# 03_POWER.net
KiCad netlist of a schematic drawn in Altium Designer
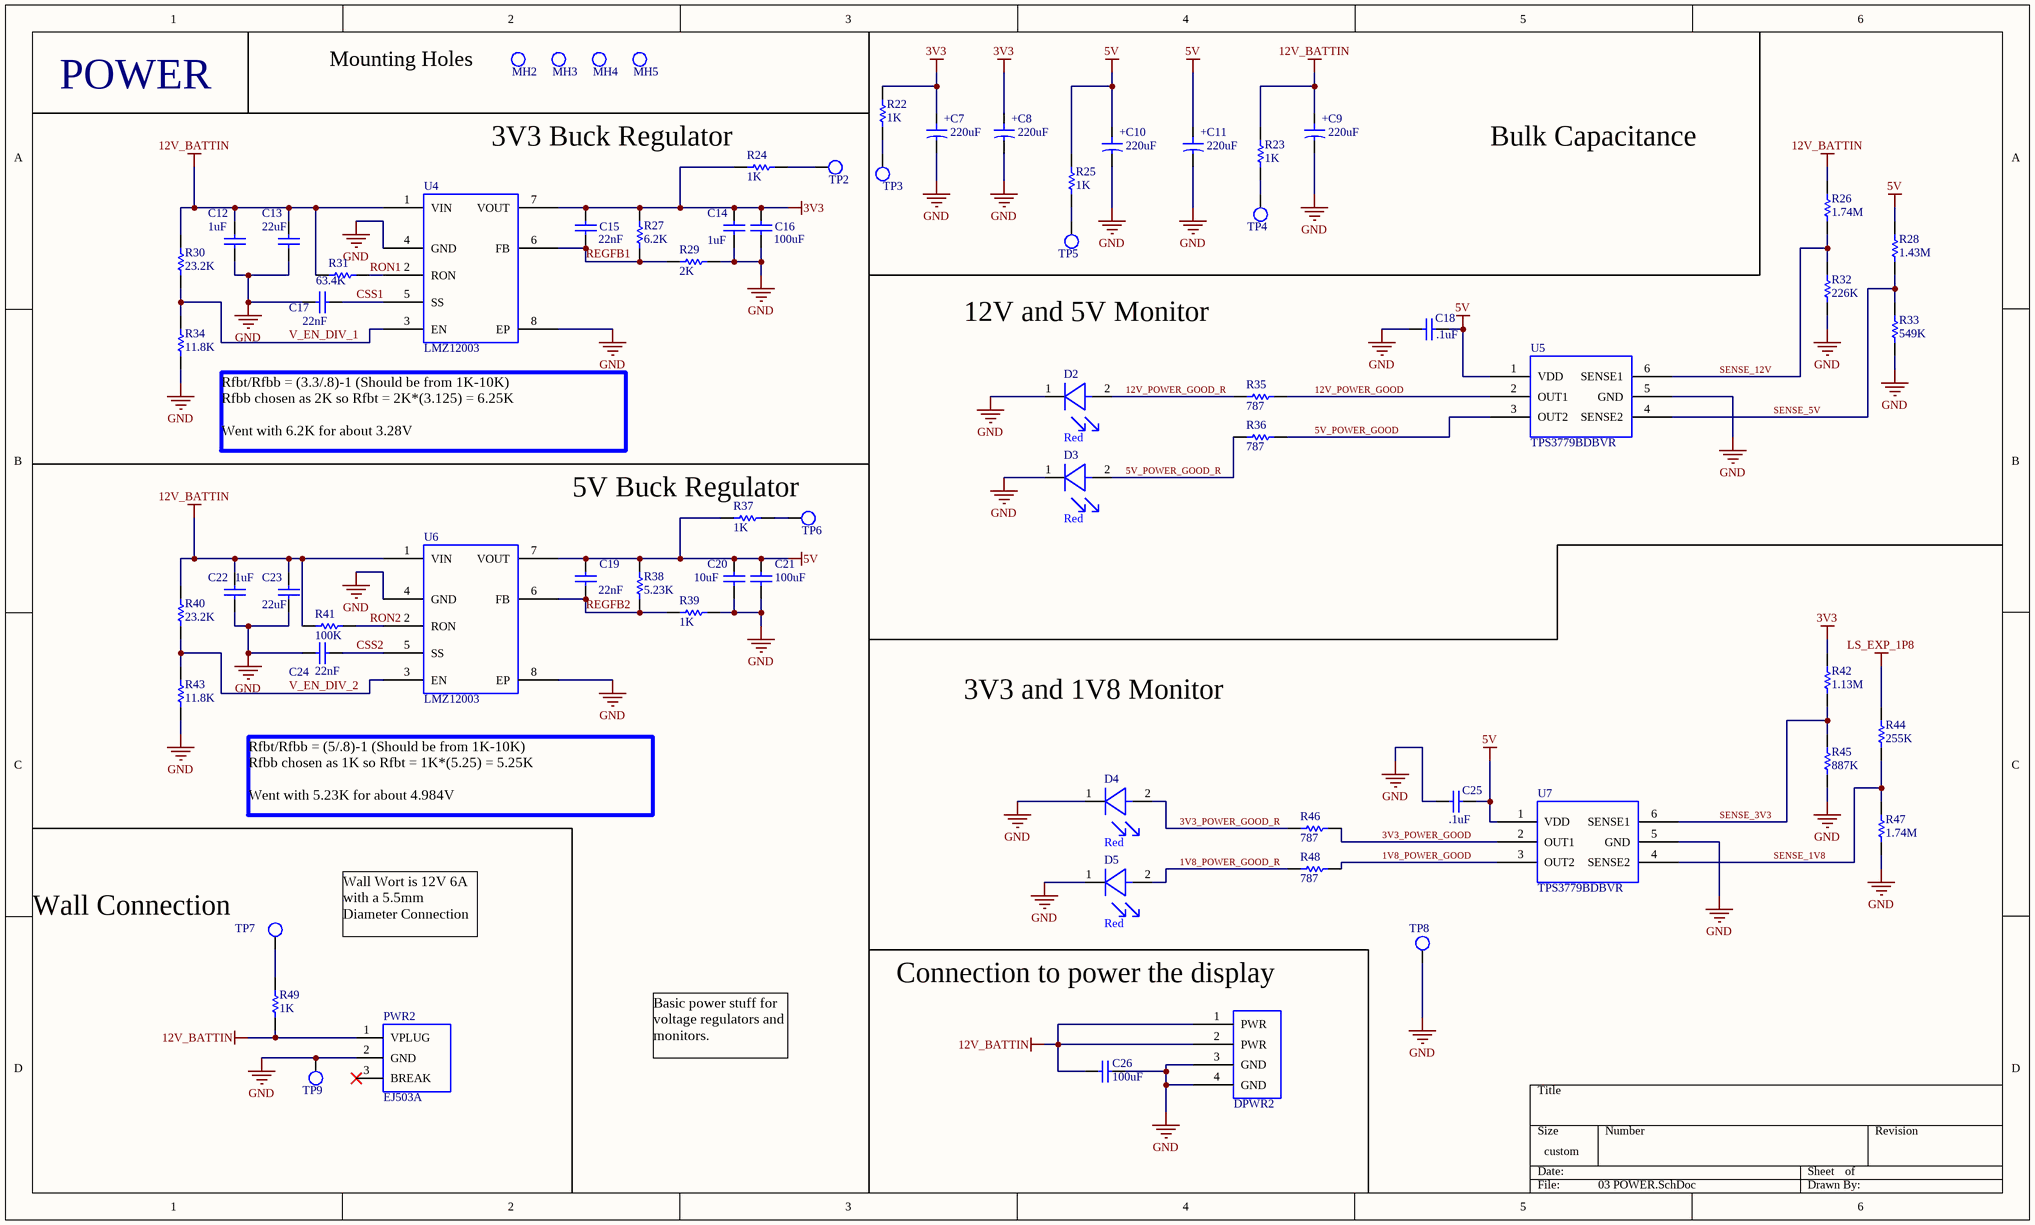
[diagram p0: 03 POWER.SchDoc]

(export (version "E")
  (design (tool "Eeschema 10.0.6"))
  (components
    (comp (ref "C7")
      (value "CAP ALUM 220UF 20% 25V SMD")
      (footprint "CAP_RADIAL")
      (fields
        (field (name "MANUFACTURER") "Nichicon")
        (field (name "MANUFACTURER PART NUMBER") "UWT1E221MNL1GS")
        (field (name "TOLERANCE") "20%")
        (field (name "CAPACITANCE") "220uF")
      )
      (libsource (lib "schlib_truman") (part "CAP_RAD_220u_25V"))
    )
    (comp (ref "C8")
      (value "CAP ALUM 220UF 20% 25V SMD")
      (footprint "CAP_RADIAL")
      (fields
        (field (name "MANUFACTURER") "Nichicon")
        (field (name "MANUFACTURER PART NUMBER") "UWT1E221MNL1GS")
        (field (name "TOLERANCE") "20%")
        (field (name "CAPACITANCE") "220uF")
      )
      (libsource (lib "schlib_truman") (part "CAP_RAD_220u_25V"))
    )
    (comp (ref "C9")
      (value "CAP ALUM 220UF 20% 25V SMD")
      (footprint "CAP_RADIAL")
      (fields
        (field (name "MANUFACTURER") "Nichicon")
        (field (name "MANUFACTURER PART NUMBER") "UWT1E221MNL1GS")
        (field (name "TOLERANCE") "20%")
        (field (name "CAPACITANCE") "220uF")
      )
      (libsource (lib "schlib_truman") (part "CAP_RAD_220u_25V"))
    )
    (comp (ref "C10")
      (value "CAP ALUM 220UF 20% 25V SMD")
      (footprint "CAP_RADIAL")
      (fields
        (field (name "MANUFACTURER") "Nichicon")
        (field (name "MANUFACTURER PART NUMBER") "UWT1E221MNL1GS")
        (field (name "TOLERANCE") "20%")
        (field (name "CAPACITANCE") "220uF")
      )
      (libsource (lib "schlib_truman") (part "CAP_RAD_220u_25V"))
    )
    (comp (ref "C11")
      (value "CAP ALUM 220UF 20% 25V SMD")
      (footprint "CAP_RADIAL")
      (fields
        (field (name "MANUFACTURER") "Nichicon")
        (field (name "MANUFACTURER PART NUMBER") "UWT1E221MNL1GS")
        (field (name "TOLERANCE") "20%")
        (field (name "CAPACITANCE") "220uF")
      )
      (libsource (lib "schlib_truman") (part "CAP_RAD_220u_25V"))
    )
    (comp (ref "C12")
      (value "1uF")
      (footprint "CAPC2012X135N")
      (description "CAP CER 1UF 100V X7S 0805")
      (fields
        (field (name "MANUFACTURER") "TDK")
        (field (name "MANUFACTURER PART NUMBER") "C2012X7S2A105K125AE")
      )
      (libsource (lib "schlib_truman") (part "CAP_0805_1u_100V"))
    )
    (comp (ref "C13")
      (value "22uF")
      (footprint "CAPC2012X135N")
      (fields
        (field (name "MANUFACTURER") "Samsung")
        (field (name "MANUFACTURER PART NUMBER") "CL21A226MAQNNNE")
        (field (name "TOLERANCE") "20%")
      )
      (libsource (lib "schlib_truman") (part "CAP_0805_22u_25V"))
    )
    (comp (ref "C14")
      (value "1uF")
      (footprint "CAPC2012X135N")
      (description "CAP CER 1UF 100V X7S 0805")
      (fields
        (field (name "MANUFACTURER") "TDK")
        (field (name "MANUFACTURER PART NUMBER") "C2012X7S2A105K125AE")
      )
      (libsource (lib "schlib_truman") (part "CAP_0805_1u_100V"))
    )
    (comp (ref "C15")
      (value "22nF")
      (footprint "CAPC2012X135N")
      (description "CAP CER 0.022UF 100V X7R 0805")
      (fields
        (field (name "MANUFACTURER") "TDK")
        (field (name "MANUFACTURER PART NUMBER") "CGJ4J2X7R2A223K125AA")
      )
      (libsource (lib "schlib_truman") (part "CAP_0805_22n_100V"))
    )
    (comp (ref "C16")
      (value "100uF")
      (footprint "FP_1210")
      (description "Cap Ceramic 100uF 10V X5R 20% SMD 1210 85C Embossed T/R")
      (fields
        (field (name "MANUFACTURER") "Murata")
        (field (name "MANUFACTURER PART NUMBER") "GRM32ER61A107ME20L")
      )
      (libsource (lib "schlib_truman") (part "CAP_1210_100u_10V"))
    )
    (comp (ref "C17")
      (value "22nF")
      (footprint "CAPC2012X135N")
      (description "CAP CER 0.022UF 100V X7R 0805")
      (fields
        (field (name "MANUFACTURER") "TDK")
        (field (name "MANUFACTURER PART NUMBER") "CGJ4J2X7R2A223K125AA")
      )
      (libsource (lib "schlib_truman") (part "CAP_0805_22n_100V"))
    )
    (comp (ref "C18")
      (value ".1uF")
      (footprint "CAPC2012X135N")
      (description "Cap Ceramic 0.1uF 250V X7T 10% SMD 0805 125C Plastic T/R")
      (fields
        (field (name "MANUFACTURER") "TDK")
        (field (name "MANUFACTURER PART NUMBER") "C2012X7T2E104K125AE")
      )
      (libsource (lib "schlib_truman") (part "CAP_0805_.1u_250V"))
    )
    (comp (ref "C19")
      (value "22nF")
      (footprint "CAPC2012X135N")
      (description "CAP CER 0.022UF 100V X7R 0805")
      (fields
        (field (name "MANUFACTURER") "TDK")
        (field (name "MANUFACTURER PART NUMBER") "CGJ4J2X7R2A223K125AA")
      )
      (libsource (lib "schlib_truman") (part "CAP_0805_22n_100V"))
    )
    (comp (ref "C20")
      (value "10uF")
      (footprint "CAPC2012X135N")
      (description "Cap Ceramic 10uF 16V X5R 10% SMD 0805 85C T/R")
      (fields
        (field (name "MANUFACTURER") "Johanson Dielectrics")
        (field (name "MANUFACTURER PART NUMBER") "160R15X106KV4E")
      )
      (libsource (lib "schlib_truman") (part "CAP_0805_10u_16V"))
    )
    (comp (ref "C21")
      (value "100uF")
      (footprint "FP_1210")
      (description "Cap Ceramic 100uF 10V X5R 20% SMD 1210 85C Embossed T/R")
      (fields
        (field (name "MANUFACTURER") "Murata")
        (field (name "MANUFACTURER PART NUMBER") "GRM32ER61A107ME20L")
      )
      (libsource (lib "schlib_truman") (part "CAP_1210_100u_10V"))
    )
    (comp (ref "C22")
      (value "1uF")
      (footprint "CAPC2012X135N")
      (description "CAP CER 1UF 100V X7S 0805")
      (fields
        (field (name "MANUFACTURER") "TDK")
        (field (name "MANUFACTURER PART NUMBER") "C2012X7S2A105K125AE")
      )
      (libsource (lib "schlib_truman") (part "CAP_0805_1u_100V"))
    )
    (comp (ref "C23")
      (value "22uF")
      (footprint "CAPC2012X135N")
      (fields
        (field (name "MANUFACTURER") "Samsung")
        (field (name "MANUFACTURER PART NUMBER") "CL21A226MAQNNNE")
        (field (name "TOLERANCE") "20%")
      )
      (libsource (lib "schlib_truman") (part "CAP_0805_22u_25V"))
    )
    (comp (ref "C24")
      (value "22nF")
      (footprint "CAPC2012X135N")
      (description "CAP CER 0.022UF 100V X7R 0805")
      (fields
        (field (name "MANUFACTURER") "TDK")
        (field (name "MANUFACTURER PART NUMBER") "CGJ4J2X7R2A223K125AA")
      )
      (libsource (lib "schlib_truman") (part "CAP_0805_22n_100V"))
    )
    (comp (ref "C25")
      (value ".1uF")
      (footprint "CAPC2012X135N")
      (description "Cap Ceramic 0.1uF 250V X7T 10% SMD 0805 125C Plastic T/R")
      (fields
        (field (name "MANUFACTURER") "TDK")
        (field (name "MANUFACTURER PART NUMBER") "C2012X7T2E104K125AE")
      )
      (libsource (lib "schlib_truman") (part "CAP_0805_.1u_250V"))
    )
    (comp (ref "C26")
      (value "100uF")
      (footprint "FP_1210")
      (description "Cap Ceramic 100uF 10V X5R 20% SMD 1210 85C Embossed T/R")
      (fields
        (field (name "MANUFACTURER") "Murata")
        (field (name "MANUFACTURER PART NUMBER") "GRM32ER61A107ME20L")
      )
      (libsource (lib "schlib_truman") (part "CAP_1210_100u_10V"))
    )
    (comp (ref "D2")
      (value "LED_RED_636nm")
      (footprint "POWERLED_FP")
      (description "Standard LEDs - SMD Surface Mount LEDs")
      (fields
        (field (name "COLOR") "Red")
        (field (name "MANUFACTURER") "Lumex")
        (field (name "MANUFACTURER PART NUMBER") "SML-LXR85SIC-TR")
      )
      (libsource (lib "schlib_truman") (part "LED_RED_636nm"))
    )
    (comp (ref "D3")
      (value "LED_RED_636nm")
      (footprint "POWERLED_FP")
      (description "Standard LEDs - SMD Surface Mount LEDs")
      (fields
        (field (name "COLOR") "Red")
        (field (name "MANUFACTURER") "Lumex")
        (field (name "MANUFACTURER PART NUMBER") "SML-LXR85SIC-TR")
      )
      (libsource (lib "schlib_truman") (part "LED_RED_636nm"))
    )
    (comp (ref "D4")
      (value "LED_RED_636nm")
      (footprint "POWERLED_FP")
      (description "Standard LEDs - SMD Surface Mount LEDs")
      (fields
        (field (name "COLOR") "Red")
        (field (name "MANUFACTURER") "Lumex")
        (field (name "MANUFACTURER PART NUMBER") "SML-LXR85SIC-TR")
      )
      (libsource (lib "schlib_truman") (part "LED_RED_636nm"))
    )
    (comp (ref "D5")
      (value "LED_RED_636nm")
      (footprint "POWERLED_FP")
      (description "Standard LEDs - SMD Surface Mount LEDs")
      (fields
        (field (name "COLOR") "Red")
        (field (name "MANUFACTURER") "Lumex")
        (field (name "MANUFACTURER PART NUMBER") "SML-LXR85SIC-TR")
      )
      (libsource (lib "schlib_truman") (part "LED_RED_636nm"))
    )
    (comp (ref "DPWR2")
      (value "Display_Power")
      (footprint "PHOENIX_4POS_1935187")
      (description "4 Position Thru Hole Connection")
      (fields
        (field (name "MANUFACTURER") "Phoenix Contact")
        (field (name "MANUFACTURER PART NUMBER") "1935187")
      )
      (libsource (lib "schlib_truman") (part "Display_Power"))
    )
    (comp (ref "MH2")
      (value "MOUNTINGHOLE")
      (footprint "MOUNTINGHOLE")
      (description "Mounting Hole For Board")
      (libsource (lib "schlib_truman") (part "MOUNTINGHOLE"))
    )
    (comp (ref "MH3")
      (value "MOUNTINGHOLE")
      (footprint "MOUNTINGHOLE")
      (description "Mounting Hole For Board")
      (libsource (lib "schlib_truman") (part "MOUNTINGHOLE"))
    )
    (comp (ref "MH4")
      (value "MOUNTINGHOLE")
      (footprint "MOUNTINGHOLE")
      (description "Mounting Hole For Board")
      (libsource (lib "schlib_truman") (part "MOUNTINGHOLE"))
    )
    (comp (ref "MH5")
      (value "MOUNTINGHOLE")
      (footprint "MOUNTINGHOLE")
      (description "Mounting Hole For Board")
      (libsource (lib "schlib_truman") (part "MOUNTINGHOLE"))
    )
    (comp (ref "PWR2")
      (value "EJ503A")
      (footprint "BARRELJACK")
      (description "DC Barrel Jack 2.1mm x 5.5mm 12V 5A")
      (fields (field (name "MANUFACTURER") "Memory Protection Devices"))
      (libsource (lib "schlib_truman") (part "EJ503A"))
    )
    (comp (ref "R22")
      (value "RES_0805_1K")
      (footprint "RES0805")
      (description "RES SMD 1K OHM 1% 1/8W 0805")
      (fields
        (field (name "MANUFACTURER") "Yageo")
        (field (name "MANUFACTURER PART NUMBER") "RC0805FR-071KL")
        (field (name "ALTIUM_UNNAMED_1") "1K")
      )
      (libsource (lib "schlib_truman") (part "RES_0805_1K"))
    )
    (comp (ref "R23")
      (value "RES_0805_1K")
      (footprint "RES0805")
      (description "RES SMD 1K OHM 1% 1/8W 0805")
      (fields
        (field (name "MANUFACTURER") "Yageo")
        (field (name "MANUFACTURER PART NUMBER") "RC0805FR-071KL")
        (field (name "ALTIUM_UNNAMED_1") "1K")
      )
      (libsource (lib "schlib_truman") (part "RES_0805_1K"))
    )
    (comp (ref "R24")
      (value "RES_0805_1K")
      (footprint "RES0805")
      (description "RES SMD 1K OHM 1% 1/8W 0805")
      (fields
        (field (name "MANUFACTURER") "Yageo")
        (field (name "MANUFACTURER PART NUMBER") "RC0805FR-071KL")
        (field (name "ALTIUM_UNNAMED_1") "1K")
      )
      (libsource (lib "schlib_truman") (part "RES_0805_1K"))
    )
    (comp (ref "R25")
      (value "RES_0805_1K")
      (footprint "RES0805")
      (description "RES SMD 1K OHM 1% 1/8W 0805")
      (fields
        (field (name "MANUFACTURER") "Yageo")
        (field (name "MANUFACTURER PART NUMBER") "RC0805FR-071KL")
        (field (name "ALTIUM_UNNAMED_1") "1K")
      )
      (libsource (lib "schlib_truman") (part "RES_0805_1K"))
    )
    (comp (ref "R26")
      (value "RES_0805_1.74M")
      (footprint "RES0805")
      (description "RES SMD 1.74M OHM 1% 1/8W 0805")
      (fields
        (field (name "ALTIUM_UNNAMED_1") "1.74M")
        (field (name "MANUFACTURER") "Yageo")
        (field (name "MANUFACTURER PART NUMBER") "RC0805FR-071M74L")
      )
      (libsource (lib "schlib_truman") (part "RES_0805_1.74M"))
    )
    (comp (ref "R27")
      (value "RES_6.2K")
      (footprint "RES0805")
      (description "Yageo RC0805 Series Thick Film Surface Mount Resistor 0805 Case 6.2k 1% 0.125W 100ppm/C")
      (fields
        (field (name "MANUFACTURER") "Yageo")
        (field (name "MANUFACTURER PART NUMBER") "RC0805FR-076K2L")
        (field (name "ALTIUM_UNNAMED_1") "6.2K")
      )
      (libsource (lib "schlib_truman") (part "RES_0805_6.2K"))
    )
    (comp (ref "R28")
      (value "RES_1.43M")
      (footprint "RES0805")
      (description "RES SMD 1.43M OHM 1% 1/8W 0805")
      (fields
        (field (name "ALTIUM_UNNAMED_1") "1.43M")
        (field (name "MANUFACTURER") "Yageo")
        (field (name "MANUFACTURER PART NUMBER") "RC0805FR-071M43L")
      )
      (libsource (lib "schlib_truman") (part "RES_0805_1.43M"))
    )
    (comp (ref "R29")
      (value "RES_0805_2K")
      (footprint "RES0805")
      (description "RES SMD 2K OHM 5% 1/8W 0805")
      (fields
        (field (name "MANUFACTURER") "Yageo")
        (field (name "MANUFACTURER PART NUMBER") "RC0805JR-072KL")
        (field (name "ALTIUM_UNNAMED_1") "2K")
      )
      (libsource (lib "schlib_truman") (part "RES_0805_2K"))
    )
    (comp (ref "R30")
      (value "RES_0805_23.2K")
      (footprint "RES0805")
      (description "RESISTOR, THICK FILM, 23.2KOHM, 125mW, ± 1%")
      (fields
        (field (name "MANUFACTURER") "Panasonic ECG")
        (field (name "MANUFACTURER PART NUMBER") "ERJ-6ENF2322V")
        (field (name "ALTIUM_UNNAMED_1") "23.2K")
      )
      (libsource (lib "schlib_truman") (part "RES_0805_23.2K"))
    )
    (comp (ref "R31")
      (value "RES_63.4K")
      (footprint "RES0805")
      (description "RES SMD 63.4K OHM 1% 1/8W 0805")
      (fields
        (field (name "MANUFACTURER") "Yageo")
        (field (name "MANUFACTURER PART NUMBER") "RC0805FR-0763K4L")
        (field (name "ALTIUM_UNNAMED_1") "63.4K")
      )
      (libsource (lib "schlib_truman") (part "RES_0805_63.4K"))
    )
    (comp (ref "R32")
      (value "RES_0805_226K")
      (footprint "RES0805")
      (description "Res Thick Film 0805 226K Ohm 1% 1/8W ±100ppm/C Molded SMD Punched Carrier T/R")
      (fields
        (field (name "ALTIUM_UNNAMED_1") "226K")
        (field (name "MANUFACTURER") "Panasonic ECG")
        (field (name "MANUFACTURER PART NUMBER") "ERJ-6ENF2263V")
      )
      (libsource (lib "schlib_truman") (part "RES_0805_226K"))
    )
    (comp (ref "R33")
      (value "RES_549K")
      (footprint "RES0805")
      (description "RES SMD 549K OHM 1% 1/8W 0805")
      (fields
        (field (name "ALTIUM_UNNAMED_1") "549K")
        (field (name "MANUFACTURER") "Vishay")
        (field (name "MANUFACTURER PART NUMBER") "CRCW0805549KFKEA")
      )
      (libsource (lib "schlib_truman") (part "RES_0805_549K"))
    )
    (comp (ref "R34")
      (value "RES_0805_11.8K")
      (footprint "RES0805")
      (description "RES SMD 11.8K OHM 1% 1/8W 0805")
      (fields
        (field (name "MANUFACTURER") "Yageo")
        (field (name "MANUFACTURER PART NUMBER") "RC0805FR-0711K8L")
        (field (name "ALTIUM_UNNAMED_1") "11.8K")
      )
      (libsource (lib "schlib_truman") (part "RES_0805_11.8K"))
    )
    (comp (ref "R35")
      (value "RES_787")
      (footprint "RES0805")
      (description "RES SMD 787 OHM 1% 1/8W 0805")
      (fields
        (field (name "MANUFACTURER") "Yageo")
        (field (name "MANUFACTURER PART NUMBER") "RC0805FR-07787RL")
        (field (name "ALTIUM_UNNAMED_1") "787")
      )
      (libsource (lib "schlib_truman") (part "RES_0805_787"))
    )
    (comp (ref "R36")
      (value "RES_787")
      (footprint "RES0805")
      (description "RES SMD 787 OHM 1% 1/8W 0805")
      (fields
        (field (name "MANUFACTURER") "Yageo")
        (field (name "MANUFACTURER PART NUMBER") "RC0805FR-07787RL")
        (field (name "ALTIUM_UNNAMED_1") "787")
      )
      (libsource (lib "schlib_truman") (part "RES_0805_787"))
    )
    (comp (ref "R37")
      (value "RES_0805_1K")
      (footprint "RES0805")
      (description "RES SMD 1K OHM 1% 1/8W 0805")
      (fields
        (field (name "MANUFACTURER") "Yageo")
        (field (name "MANUFACTURER PART NUMBER") "RC0805FR-071KL")
        (field (name "ALTIUM_UNNAMED_1") "1K")
      )
      (libsource (lib "schlib_truman") (part "RES_0805_1K"))
    )
    (comp (ref "R38")
      (value "RES_5.23K")
      (footprint "RES0805")
      (description "Thick Film Resistors 5.23K OHM 1%")
      (fields
        (field (name "MANUFACTURER") "Yageo")
        (field (name "MANUFACTURER PART NUMBER") "RC0805FR-075K23L")
        (field (name "ALTIUM_UNNAMED_1") "5.23K")
      )
      (libsource (lib "schlib_truman") (part "RES_0805_5.23K"))
    )
    (comp (ref "R39")
      (value "RES_0805_1K")
      (footprint "RES0805")
      (description "RES SMD 1K OHM 1% 1/8W 0805")
      (fields
        (field (name "MANUFACTURER") "Yageo")
        (field (name "MANUFACTURER PART NUMBER") "RC0805FR-071KL")
        (field (name "ALTIUM_UNNAMED_1") "1K")
      )
      (libsource (lib "schlib_truman") (part "RES_0805_1K"))
    )
    (comp (ref "R40")
      (value "RES_0805_23.2K")
      (footprint "RES0805")
      (description "RESISTOR, THICK FILM, 23.2KOHM, 125mW, ± 1%")
      (fields
        (field (name "MANUFACTURER") "Panasonic ECG")
        (field (name "MANUFACTURER PART NUMBER") "ERJ-6ENF2322V")
        (field (name "ALTIUM_UNNAMED_1") "23.2K")
      )
      (libsource (lib "schlib_truman") (part "RES_0805_23.2K"))
    )
    (comp (ref "R41")
      (value "RES_0805_100K")
      (footprint "RES0805")
      (description "Res Thick Film 0805 100K Ohm 1% 0.125W(1/8W) ±100ppm/C Molded SMD Automotive Punched T/R")
      (fields
        (field (name "MANUFACTURER") "Panasonic ECG")
        (field (name "MANUFACTURER PART NUMBER") "ERJ-6ENF1003V")
        (field (name "ALTIUM_UNNAMED_1") "100K")
      )
      (libsource (lib "schlib_truman") (part "RES_0805_100K"))
    )
    (comp (ref "R42")
      (value "RES_1.13M")
      (footprint "RES0805")
      (description "Res Thick Film 0805 1.13M Ohm 1% 1/8W 100ppm/C Molded SMD Punched Carrier T/R")
      (fields
        (field (name "ALTIUM_UNNAMED_1") "1.13M")
        (field (name "MANUFACTURER") "Panasonic")
        (field (name "MANUFACTURER PART NUMBER") "ERJ-6ENF1134V")
      )
      (libsource (lib "schlib_truman") (part "RES_0805_1.13M"))
    )
    (comp (ref "R43")
      (value "RES_0805_11.8K")
      (footprint "RES0805")
      (description "RES SMD 11.8K OHM 1% 1/8W 0805")
      (fields
        (field (name "MANUFACTURER") "Yageo")
        (field (name "MANUFACTURER PART NUMBER") "RC0805FR-0711K8L")
        (field (name "ALTIUM_UNNAMED_1") "11.8K")
      )
      (libsource (lib "schlib_truman") (part "RES_0805_11.8K"))
    )
    (comp (ref "R44")
      (value "RES_0805_255K")
      (footprint "RES0805")
      (description "RES SMD 255K OHM 1% 1/8W 0805")
      (fields
        (field (name "MANUFACTURER") "Yageo")
        (field (name "MANUFACTURER PART NUMBER") "RC0805FR-07255KL")
        (field (name "ALTIUM_UNNAMED_1") "255K")
      )
      (libsource (lib "schlib_truman") (part "RES_0805_255K"))
    )
    (comp (ref "R45")
      (value "RES_887K")
      (footprint "RES0805")
      (description "Thick Film Resistors - SMD 887K OHM 1%")
      (fields
        (field (name "ALTIUM_UNNAMED_1") "887K")
        (field (name "MANUFACTURER") "Yageo")
        (field (name "MANUFACTURER PART NUMBER") "RC0805FR-07887KL")
      )
      (libsource (lib "schlib_truman") (part "RES_0805_887K"))
    )
    (comp (ref "R46")
      (value "RES_787")
      (footprint "RES0805")
      (description "RES SMD 787 OHM 1% 1/8W 0805")
      (fields
        (field (name "MANUFACTURER") "Yageo")
        (field (name "MANUFACTURER PART NUMBER") "RC0805FR-07787RL")
        (field (name "ALTIUM_UNNAMED_1") "787")
      )
      (libsource (lib "schlib_truman") (part "RES_0805_787"))
    )
    (comp (ref "R47")
      (value "RES_0805_1.74M")
      (footprint "RES0805")
      (description "RES SMD 1.74M OHM 1% 1/8W 0805")
      (fields
        (field (name "ALTIUM_UNNAMED_1") "1.74M")
        (field (name "MANUFACTURER") "Yageo")
        (field (name "MANUFACTURER PART NUMBER") "RC0805FR-071M74L")
      )
      (libsource (lib "schlib_truman") (part "RES_0805_1.74M"))
    )
    (comp (ref "R48")
      (value "RES_787")
      (footprint "RES0805")
      (description "RES SMD 787 OHM 1% 1/8W 0805")
      (fields
        (field (name "MANUFACTURER") "Yageo")
        (field (name "MANUFACTURER PART NUMBER") "RC0805FR-07787RL")
        (field (name "ALTIUM_UNNAMED_1") "787")
      )
      (libsource (lib "schlib_truman") (part "RES_0805_787"))
    )
    (comp (ref "R49")
      (value "RES_0805_1K")
      (footprint "RES0805")
      (description "RES SMD 1K OHM 1% 1/8W 0805")
      (fields
        (field (name "MANUFACTURER") "Yageo")
        (field (name "MANUFACTURER PART NUMBER") "RC0805FR-071KL")
        (field (name "ALTIUM_UNNAMED_1") "1K")
      )
      (libsource (lib "schlib_truman") (part "RES_0805_1K"))
    )
    (comp (ref "TP2")
      (value "TP")
      (footprint "TestPoint_0805")
      (description "Testpoint_0805")
      (fields
        (field (name "MANUFACTURER") "TE Connectivity")
        (field (name "MANUFACTURER PART NUMBER") "1625854-2")
      )
      (libsource (lib "schlib_truman") (part "TP"))
    )
    (comp (ref "TP3")
      (value "TP")
      (footprint "TestPoint_0805")
      (description "Testpoint_0805")
      (fields
        (field (name "MANUFACTURER") "TE Connectivity")
        (field (name "MANUFACTURER PART NUMBER") "1625854-2")
      )
      (libsource (lib "schlib_truman") (part "TP"))
    )
    (comp (ref "TP4")
      (value "TP")
      (footprint "TestPoint_0805")
      (description "Testpoint_0805")
      (fields
        (field (name "MANUFACTURER") "TE Connectivity")
        (field (name "MANUFACTURER PART NUMBER") "1625854-2")
      )
      (libsource (lib "schlib_truman") (part "TP"))
    )
    (comp (ref "TP5")
      (value "TP")
      (footprint "TestPoint_0805")
      (description "Testpoint_0805")
      (fields
        (field (name "MANUFACTURER") "TE Connectivity")
        (field (name "MANUFACTURER PART NUMBER") "1625854-2")
      )
      (libsource (lib "schlib_truman") (part "TP"))
    )
    (comp (ref "TP6")
      (value "TP")
      (footprint "TestPoint_0805")
      (description "Testpoint_0805")
      (fields
        (field (name "MANUFACTURER") "TE Connectivity")
        (field (name "MANUFACTURER PART NUMBER") "1625854-2")
      )
      (libsource (lib "schlib_truman") (part "TP"))
    )
    (comp (ref "TP7")
      (value "TP")
      (footprint "TestPoint_0805")
      (description "Testpoint_0805")
      (fields
        (field (name "MANUFACTURER") "TE Connectivity")
        (field (name "MANUFACTURER PART NUMBER") "1625854-2")
      )
      (libsource (lib "schlib_truman") (part "TP"))
    )
    (comp (ref "TP8")
      (value "TP")
      (footprint "TestPoint_0805")
      (description "Testpoint_0805")
      (fields
        (field (name "MANUFACTURER") "TE Connectivity")
        (field (name "MANUFACTURER PART NUMBER") "1625854-2")
      )
      (libsource (lib "schlib_truman") (part "TP"))
    )
    (comp (ref "TP9")
      (value "TP")
      (footprint "TestPoint_0805")
      (description "Testpoint_0805")
      (fields
        (field (name "MANUFACTURER") "TE Connectivity")
        (field (name "MANUFACTURER PART NUMBER") "1625854-2")
      )
      (libsource (lib "schlib_truman") (part "TP"))
    )
    (comp (ref "U4")
      (value "LMZ12003")
      (footprint "TO-PMOD-7")
      (description "POWER MODULE, TO-PMOD-7, FULL REEL")
      (fields
        (field (name "MANUFACTURER") "Texas Instruments")
        (field (name "MANUFACTURER PART NUMBER") "LMZ12003TZ-ADJ/NOPB")
      )
      (libsource (lib "schlib_truman") (part "LMZ12003"))
    )
    (comp (ref "U5")
      (value "TPS3779BDBVR")
      (footprint "DBV (R-PDSO-G6)")
      (description "Voltage Detector, Active-Low, Push-Pull Reset, 2-Monitors, 1.5V-6.5Vin, SOT-23-6")
      (fields
        (field (name "MANUFACTURER") "Texas Instruments")
        (field (name "MANUFACTURER PART NUMBER") "TPS3779BDBVT")
      )
      (libsource (lib "schlib_truman") (part "TPS3779BDBVR"))
    )
    (comp (ref "U6")
      (value "LMZ12003")
      (footprint "TO-PMOD-7")
      (description "POWER MODULE, TO-PMOD-7, FULL REEL")
      (fields
        (field (name "MANUFACTURER") "Texas Instruments")
        (field (name "MANUFACTURER PART NUMBER") "LMZ12003TZ-ADJ/NOPB")
      )
      (libsource (lib "schlib_truman") (part "LMZ12003"))
    )
    (comp (ref "U7")
      (value "TPS3779BDBVR")
      (footprint "DBV (R-PDSO-G6)")
      (description "Voltage Detector, Active-Low, Push-Pull Reset, 2-Monitors, 1.5V-6.5Vin, SOT-23-6")
      (fields
        (field (name "MANUFACTURER") "Texas Instruments")
        (field (name "MANUFACTURER PART NUMBER") "TPS3779BDBVT")
      )
      (libsource (lib "schlib_truman") (part "TPS3779BDBVR"))
    )
  )
  (nets
    (net (code "1") (name "/1V8_POWER_GOOD") (class "Default")
      (node (ref "R48") (pin "1") (pinfunction "1_1") (pintype "passive"))
      (node (ref "U7") (pin "3") (pinfunction "OUT2_3") (pintype "passive"))
    )
    (net (code "2") (name "/1V8_POWER_GOOD_R") (class "Default")
      (node (ref "D5") (pin "2") (pinfunction "Anode_2") (pintype "passive"))
      (node (ref "R48") (pin "2") (pinfunction "2_2") (pintype "passive"))
    )
    (net (code "3") (name "/3V3_POWER_GOOD") (class "Default")
      (node (ref "R46") (pin "1") (pinfunction "1_1") (pintype "passive"))
      (node (ref "U7") (pin "2") (pinfunction "OUT1_2") (pintype "passive"))
    )
    (net (code "4") (name "/3V3_POWER_GOOD_R") (class "Default")
      (node (ref "D4") (pin "2") (pinfunction "Anode_2") (pintype "passive"))
      (node (ref "R46") (pin "2") (pinfunction "2_2") (pintype "passive"))
    )
    (net (code "5") (name "/5V_POWER_GOOD") (class "Default")
      (node (ref "R36") (pin "2") (pinfunction "2_2") (pintype "passive"))
      (node (ref "U5") (pin "3") (pinfunction "OUT2_3") (pintype "passive"))
    )
    (net (code "6") (name "/5V_POWER_GOOD_R") (class "Default")
      (node (ref "D3") (pin "2") (pinfunction "Anode_2") (pintype "passive"))
      (node (ref "R36") (pin "1") (pinfunction "1_1") (pintype "passive"))
    )
    (net (code "7") (name "/12V_POWER_GOOD") (class "Default")
      (node (ref "R35") (pin "2") (pinfunction "2_2") (pintype "passive"))
      (node (ref "U5") (pin "2") (pinfunction "OUT1_2") (pintype "passive"))
    )
    (net (code "8") (name "/12V_POWER_GOOD_R") (class "Default")
      (node (ref "D2") (pin "2") (pinfunction "Anode_2") (pintype "passive"))
      (node (ref "R35") (pin "1") (pinfunction "1_1") (pintype "passive"))
    )
    (net (code "9") (name "/CSS1") (class "Default")
      (node (ref "C17") (pin "2") (pinfunction "2_2") (pintype "passive"))
      (node (ref "U4") (pin "5") (pinfunction "SS_5") (pintype "passive"))
    )
    (net (code "10") (name "/CSS2") (class "Default")
      (node (ref "C24") (pin "2") (pinfunction "2_2") (pintype "passive"))
      (node (ref "U6") (pin "5") (pinfunction "SS_5") (pintype "passive"))
    )
    (net (code "11") (name "/REGFB1") (class "Default")
      (node (ref "C15") (pin "1") (pinfunction "1_1") (pintype "passive"))
      (node (ref "R27") (pin "1") (pinfunction "1_1") (pintype "passive"))
      (node (ref "R29") (pin "1") (pinfunction "1_1") (pintype "passive"))
      (node (ref "U4") (pin "6") (pinfunction "FB_6") (pintype "passive"))
    )
    (net (code "12") (name "/REGFB2") (class "Default")
      (node (ref "C19") (pin "1") (pinfunction "1_1") (pintype "passive"))
      (node (ref "R38") (pin "1") (pinfunction "1_1") (pintype "passive"))
      (node (ref "R39") (pin "1") (pinfunction "1_1") (pintype "passive"))
      (node (ref "U6") (pin "6") (pinfunction "FB_6") (pintype "passive"))
    )
    (net (code "13") (name "/RON1") (class "Default")
      (node (ref "R31") (pin "2") (pinfunction "2_2") (pintype "passive"))
      (node (ref "U4") (pin "2") (pinfunction "RON_2") (pintype "passive"))
    )
    (net (code "14") (name "/RON2") (class "Default")
      (node (ref "R41") (pin "2") (pinfunction "2_2") (pintype "passive"))
      (node (ref "U6") (pin "2") (pinfunction "RON_2") (pintype "passive"))
    )
    (net (code "15") (name "/SENSE_1V8") (class "Default")
      (node (ref "R44") (pin "1") (pinfunction "1_1") (pintype "passive"))
      (node (ref "R47") (pin "2") (pinfunction "2_2") (pintype "passive"))
      (node (ref "U7") (pin "4") (pinfunction "SENSE2_4") (pintype "passive"))
    )
    (net (code "16") (name "/SENSE_3V3") (class "Default")
      (node (ref "R42") (pin "1") (pinfunction "1_1") (pintype "passive"))
      (node (ref "R45") (pin "2") (pinfunction "2_2") (pintype "passive"))
      (node (ref "U7") (pin "6") (pinfunction "SENSE1_6") (pintype "passive"))
    )
    (net (code "17") (name "/SENSE_5V") (class "Default")
      (node (ref "R28") (pin "1") (pinfunction "1_1") (pintype "passive"))
      (node (ref "R33") (pin "2") (pinfunction "2_2") (pintype "passive"))
      (node (ref "U5") (pin "4") (pinfunction "SENSE2_4") (pintype "passive"))
    )
    (net (code "18") (name "/SENSE_12V") (class "Default")
      (node (ref "R26") (pin "1") (pinfunction "1_1") (pintype "passive"))
      (node (ref "R32") (pin "2") (pinfunction "2_2") (pintype "passive"))
      (node (ref "U5") (pin "6") (pinfunction "SENSE1_6") (pintype "passive"))
    )
    (net (code "19") (name "/V_EN_DIV_1") (class "Default")
      (node (ref "R30") (pin "1") (pinfunction "1_1") (pintype "passive"))
      (node (ref "R34") (pin "2") (pinfunction "2_2") (pintype "passive"))
      (node (ref "U4") (pin "3") (pinfunction "EN_3") (pintype "passive"))
    )
    (net (code "20") (name "/V_EN_DIV_2") (class "Default")
      (node (ref "R40") (pin "1") (pinfunction "1_1") (pintype "passive"))
      (node (ref "R43") (pin "2") (pinfunction "2_2") (pintype "passive"))
      (node (ref "U6") (pin "3") (pinfunction "EN_3") (pintype "passive"))
    )
    (net (code "21") (name "3V3") (class "Default")
      (node (ref "C14") (pin "2") (pinfunction "2_2") (pintype "passive"))
      (node (ref "C15") (pin "2") (pinfunction "2_2") (pintype "passive"))
      (node (ref "C16") (pin "2") (pinfunction "2_2") (pintype "passive"))
      (node (ref "C7") (pin "1") (pinfunction "1_1") (pintype "passive"))
      (node (ref "C8") (pin "1") (pinfunction "1_1") (pintype "passive"))
      (node (ref "R22") (pin "1") (pinfunction "1_1") (pintype "passive"))
      (node (ref "R24") (pin "2") (pinfunction "2_2") (pintype "passive"))
      (node (ref "R27") (pin "2") (pinfunction "2_2") (pintype "passive"))
      (node (ref "R42") (pin "2") (pinfunction "2_2") (pintype "passive"))
      (node (ref "U4") (pin "7") (pinfunction "VOUT_7") (pintype "passive"))
    )
    (net (code "22") (name "5V") (class "Default")
      (node (ref "C10") (pin "1") (pinfunction "1_1") (pintype "passive"))
      (node (ref "C11") (pin "1") (pinfunction "1_1") (pintype "passive"))
      (node (ref "C18") (pin "2") (pinfunction "2_2") (pintype "passive"))
      (node (ref "C19") (pin "2") (pinfunction "2_2") (pintype "passive"))
      (node (ref "C20") (pin "2") (pinfunction "2_2") (pintype "passive"))
      (node (ref "C21") (pin "2") (pinfunction "2_2") (pintype "passive"))
      (node (ref "C25") (pin "2") (pinfunction "2_2") (pintype "passive"))
      (node (ref "R25") (pin "1") (pinfunction "1_1") (pintype "passive"))
      (node (ref "R28") (pin "2") (pinfunction "2_2") (pintype "passive"))
      (node (ref "R37") (pin "2") (pinfunction "2_2") (pintype "passive"))
      (node (ref "R38") (pin "2") (pinfunction "2_2") (pintype "passive"))
      (node (ref "U5") (pin "1") (pinfunction "VDD_1") (pintype "passive"))
      (node (ref "U6") (pin "7") (pinfunction "VOUT_7") (pintype "passive"))
      (node (ref "U7") (pin "1") (pinfunction "VDD_1") (pintype "passive"))
    )
    (net (code "23") (name "12V_BATTIN") (class "Default")
      (node (ref "C12") (pin "2") (pinfunction "2_2") (pintype "passive"))
      (node (ref "C13") (pin "2") (pinfunction "2_2") (pintype "passive"))
      (node (ref "C22") (pin "2") (pinfunction "2_2") (pintype "passive"))
      (node (ref "C23") (pin "2") (pinfunction "2_2") (pintype "passive"))
      (node (ref "C26") (pin "1") (pinfunction "1_1") (pintype "passive"))
      (node (ref "C9") (pin "1") (pinfunction "1_1") (pintype "passive"))
      (node (ref "DPWR2") (pin "1") (pinfunction "PWR_1") (pintype "passive"))
      (node (ref "DPWR2") (pin "2") (pinfunction "PWR_2") (pintype "passive"))
      (node (ref "PWR2") (pin "1") (pinfunction "VPLUG_1") (pintype "passive"))
      (node (ref "R23") (pin "1") (pinfunction "1_1") (pintype "passive"))
      (node (ref "R26") (pin "2") (pinfunction "2_2") (pintype "passive"))
      (node (ref "R30") (pin "2") (pinfunction "2_2") (pintype "passive"))
      (node (ref "R31") (pin "1") (pinfunction "1_1") (pintype "passive"))
      (node (ref "R40") (pin "2") (pinfunction "2_2") (pintype "passive"))
      (node (ref "R41") (pin "1") (pinfunction "1_1") (pintype "passive"))
      (node (ref "R49") (pin "1") (pinfunction "1_1") (pintype "passive"))
      (node (ref "U4") (pin "1") (pinfunction "VIN_1") (pintype "passive"))
      (node (ref "U6") (pin "1") (pinfunction "VIN_1") (pintype "passive"))
    )
    (net (code "24") (name "GND") (class "Default")
      (node (ref "C10") (pin "2") (pinfunction "2_2") (pintype "passive"))
      (node (ref "C11") (pin "2") (pinfunction "2_2") (pintype "passive"))
      (node (ref "C12") (pin "1") (pinfunction "1_1") (pintype "passive"))
      (node (ref "C13") (pin "1") (pinfunction "1_1") (pintype "passive"))
      (node (ref "C14") (pin "1") (pinfunction "1_1") (pintype "passive"))
      (node (ref "C16") (pin "1") (pinfunction "1_1") (pintype "passive"))
      (node (ref "C17") (pin "1") (pinfunction "1_1") (pintype "passive"))
      (node (ref "C18") (pin "1") (pinfunction "1_1") (pintype "passive"))
      (node (ref "C20") (pin "1") (pinfunction "1_1") (pintype "passive"))
      (node (ref "C21") (pin "1") (pinfunction "1_1") (pintype "passive"))
      (node (ref "C22") (pin "1") (pinfunction "1_1") (pintype "passive"))
      (node (ref "C23") (pin "1") (pinfunction "1_1") (pintype "passive"))
      (node (ref "C24") (pin "1") (pinfunction "1_1") (pintype "passive"))
      (node (ref "C25") (pin "1") (pinfunction "1_1") (pintype "passive"))
      (node (ref "C26") (pin "2") (pinfunction "2_2") (pintype "passive"))
      (node (ref "C7") (pin "2") (pinfunction "2_2") (pintype "passive"))
      (node (ref "C8") (pin "2") (pinfunction "2_2") (pintype "passive"))
      (node (ref "C9") (pin "2") (pinfunction "2_2") (pintype "passive"))
      (node (ref "D2") (pin "1") (pinfunction "Cathode_1") (pintype "passive"))
      (node (ref "D3") (pin "1") (pinfunction "Cathode_1") (pintype "passive"))
      (node (ref "D4") (pin "1") (pinfunction "Cathode_1") (pintype "passive"))
      (node (ref "D5") (pin "1") (pinfunction "Cathode_1") (pintype "passive"))
      (node (ref "DPWR2") (pin "3") (pinfunction "GND_3") (pintype "passive"))
      (node (ref "DPWR2") (pin "4") (pinfunction "GND_4") (pintype "passive"))
      (node (ref "PWR2") (pin "2") (pinfunction "GND_2") (pintype "passive"))
      (node (ref "R29") (pin "2") (pinfunction "2_2") (pintype "passive"))
      (node (ref "R32") (pin "1") (pinfunction "1_1") (pintype "passive"))
      (node (ref "R33") (pin "1") (pinfunction "1_1") (pintype "passive"))
      (node (ref "R34") (pin "1") (pinfunction "1_1") (pintype "passive"))
      (node (ref "R39") (pin "2") (pinfunction "2_2") (pintype "passive"))
      (node (ref "R43") (pin "1") (pinfunction "1_1") (pintype "passive"))
      (node (ref "R45") (pin "1") (pinfunction "1_1") (pintype "passive"))
      (node (ref "R47") (pin "1") (pinfunction "1_1") (pintype "passive"))
      (node (ref "TP8") (pin "1") (pintype "passive"))
      (node (ref "TP9") (pin "1") (pintype "passive"))
      (node (ref "U4") (pin "4") (pinfunction "GND_4") (pintype "passive"))
      (node (ref "U4") (pin "8") (pinfunction "EP_8") (pintype "passive"))
      (node (ref "U5") (pin "5") (pinfunction "GND_5") (pintype "passive"))
      (node (ref "U6") (pin "4") (pinfunction "GND_4") (pintype "passive"))
      (node (ref "U6") (pin "8") (pinfunction "EP_8") (pintype "passive"))
      (node (ref "U7") (pin "5") (pinfunction "GND_5") (pintype "passive"))
    )
    (net (code "25") (name "LS_EXP_1P8") (class "Default")
      (node (ref "R44") (pin "2") (pinfunction "2_2") (pintype "passive"))
    )
    (net (code "26") (name "Net-(R22-Pad2)") (class "Default")
      (node (ref "R22") (pin "2") (pinfunction "2_2") (pintype "passive"))
      (node (ref "TP3") (pin "1") (pintype "passive"))
    )
    (net (code "27") (name "Net-(R23-Pad2)") (class "Default")
      (node (ref "R23") (pin "2") (pinfunction "2_2") (pintype "passive"))
      (node (ref "TP4") (pin "1") (pintype "passive"))
    )
    (net (code "28") (name "Net-(R24-Pad1)") (class "Default")
      (node (ref "R24") (pin "1") (pinfunction "1_1") (pintype "passive"))
      (node (ref "TP2") (pin "1") (pintype "passive"))
    )
    (net (code "29") (name "Net-(R25-Pad2)") (class "Default")
      (node (ref "R25") (pin "2") (pinfunction "2_2") (pintype "passive"))
      (node (ref "TP5") (pin "1") (pintype "passive"))
    )
    (net (code "30") (name "Net-(R37-Pad1)") (class "Default")
      (node (ref "R37") (pin "1") (pinfunction "1_1") (pintype "passive"))
      (node (ref "TP6") (pin "1") (pintype "passive"))
    )
    (net (code "31") (name "Net-(R49-Pad2)") (class "Default")
      (node (ref "R49") (pin "2") (pinfunction "2_2") (pintype "passive"))
      (node (ref "TP7") (pin "1") (pintype "passive"))
    )
    (net (code "32") (name "unconnected-(PWR2-BREAK-Pad3)") (class "Default")
      (node (ref "PWR2") (pin "3") (pinfunction "BREAK_3") (pintype "passive+no_connect"))
    )
  )
)
